# CCDGluing.net
KiCad netlist of a schematic drawn in EAGLE
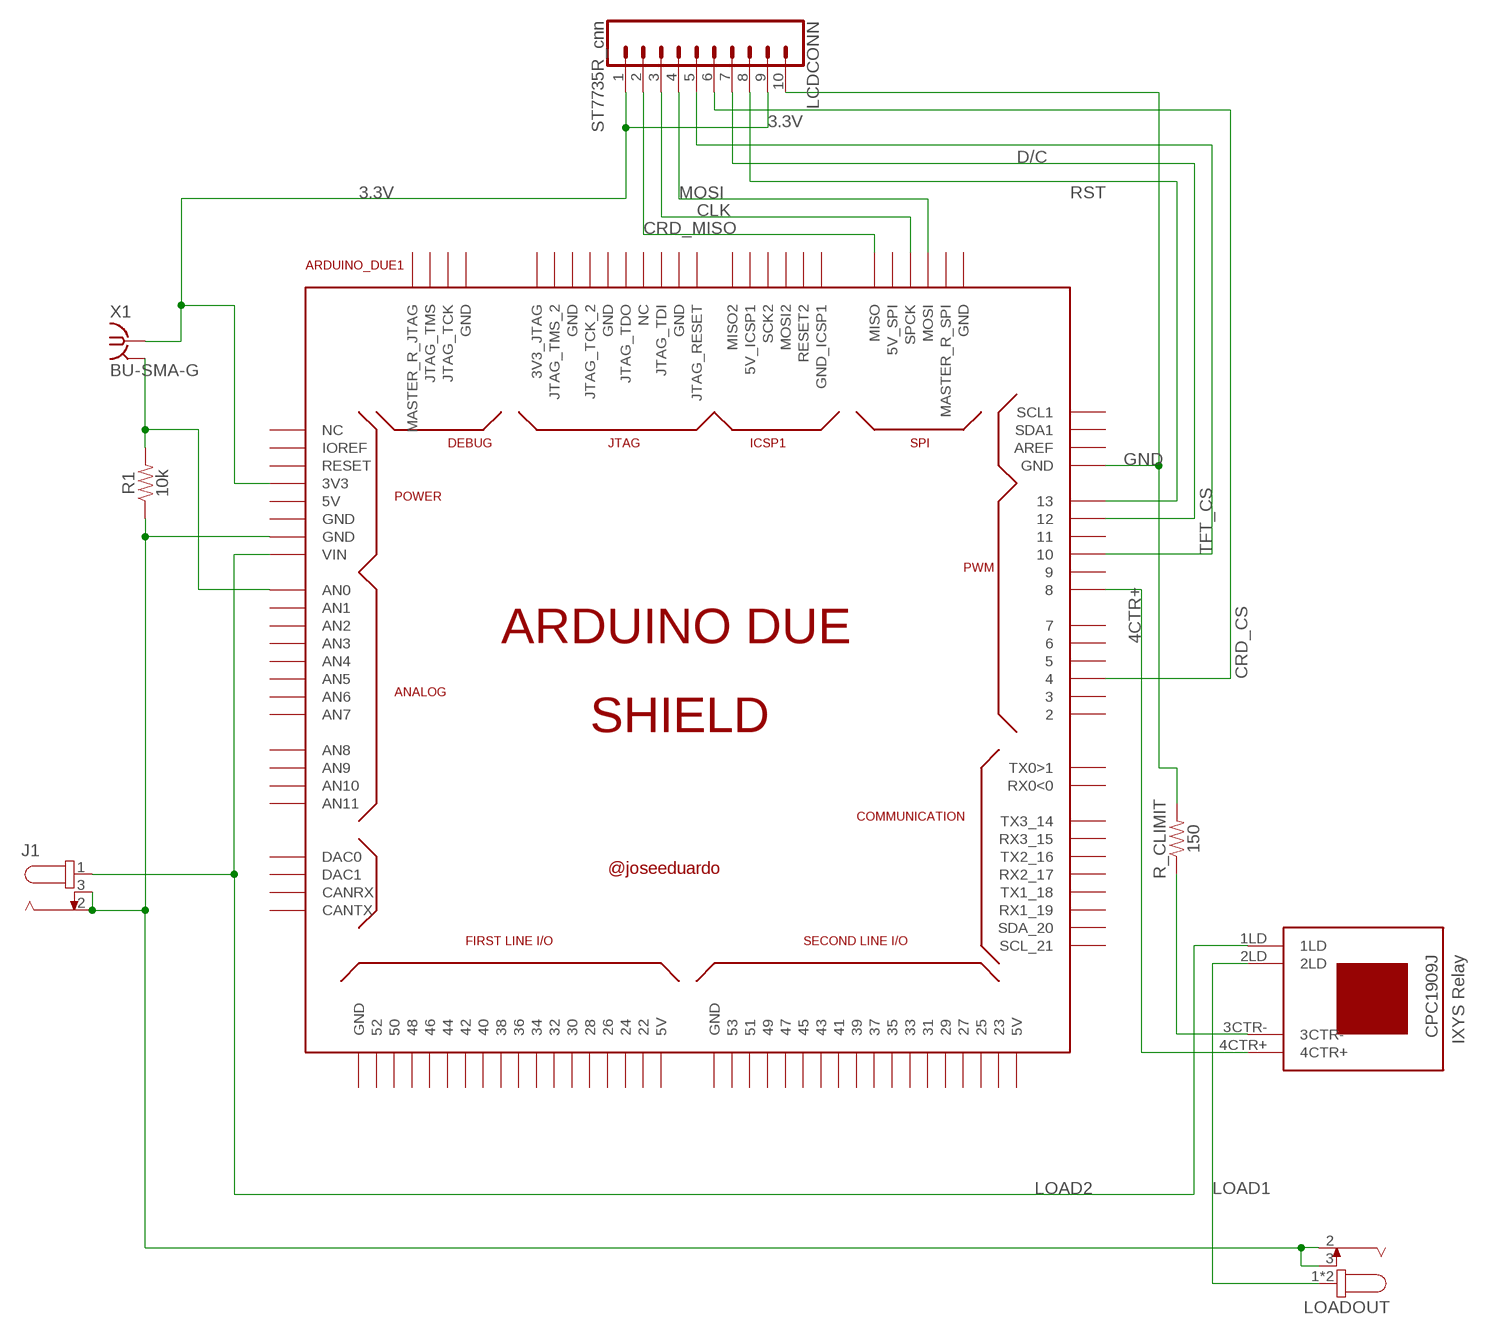
[diagram p0: schematic, sheet 1]

(export (version "E")
  (design (tool "Eeschema 10.0.6"))
  (components
    (comp (ref "ARDUINO_DUE1")
      (value "ARDUINO_DUE_SHIELD")
      (footprint "eagle-import:ARDUINO_DUE_SHIELD")
      (libsource (lib "eagle-import") (part "ARDUINO_DUE_SHIELD"))
    )
    (comp (ref "J1")
      (value "694106105102")
      (footprint "eagle-import:69410X105102")
      (libsource (lib "eagle-import") (part "694106105102"))
    )
    (comp (ref "K1")
      (value "CPC1909J")
      (footprint "eagle-import:CPC1909J")
      (libsource (lib "eagle-import") (part "CPC1909J"))
    )
    (comp (ref "LCDCONN")
      (value "ST7735R_cnn")
      (footprint "eagle-import:1X10")
      (libsource (lib "eagle-import") (part "CONN_10{dblquote}"))
    )
    (comp (ref "LOADOUT")
      (value "694103107102")
      (footprint "eagle-import:69410X107102")
      (libsource (lib "eagle-import") (part "694103107102"))
    )
    (comp (ref "R1")
      (value "10k")
      (footprint "eagle-import:0603")
      (libsource (lib "eagle-import") (part "10KOHM-0603-1/10W-1%"))
    )
    (comp (ref "R_CLIMIT")
      (value "150")
      (footprint "eagle-import:0603")
      (libsource (lib "eagle-import") (part "150OHM-0603-1/10W-1%"))
    )
    (comp (ref "X1")
      (value "BU-SMA-G")
      (footprint "eagle-import:BU-SMA-G")
      (libsource (lib "eagle-import") (part "BU-SMA-G"))
    )
  )
  (nets
    (net (code "1") (name "/3.3V") (class "Default")
      (node (ref "ARDUINO_DUE1") (pin "3V3") (pinfunction "3V3_3V3") (pintype "bidirectional"))
      (node (ref "LCDCONN") (pin "1") (pinfunction "1_1") (pintype "passive"))
      (node (ref "LCDCONN") (pin "9") (pinfunction "9_9") (pintype "passive"))
      (node (ref "X1") (pin "1") (pinfunction "1_1") (pintype "passive"))
    )
    (net (code "2") (name "/4CTR+") (class "Default")
      (node (ref "ARDUINO_DUE1") (pin "8") (pinfunction "8_8") (pintype "bidirectional"))
      (node (ref "K1") (pin "4CTR+") (pinfunction "4CTR+_4CTR+") (pintype "bidirectional"))
    )
    (net (code "3") (name "/CLK") (class "Default")
      (node (ref "ARDUINO_DUE1") (pin "SPCK") (pinfunction "SPCK_SPCK") (pintype "bidirectional"))
      (node (ref "LCDCONN") (pin "3") (pinfunction "3_3") (pintype "passive"))
    )
    (net (code "4") (name "/CRD_CS") (class "Default")
      (node (ref "ARDUINO_DUE1") (pin "4") (pinfunction "4_4") (pintype "bidirectional"))
      (node (ref "LCDCONN") (pin "6") (pinfunction "6_6") (pintype "passive"))
    )
    (net (code "5") (name "/CRD_MISO") (class "Default")
      (node (ref "ARDUINO_DUE1") (pin "MISO") (pinfunction "MISO_MISO") (pintype "bidirectional"))
      (node (ref "LCDCONN") (pin "2") (pinfunction "2_2") (pintype "passive"))
    )
    (net (code "6") (name "/D{slash}C") (class "Default")
      (node (ref "ARDUINO_DUE1") (pin "12") (pinfunction "12_12") (pintype "bidirectional"))
      (node (ref "LCDCONN") (pin "7") (pinfunction "7_7") (pintype "passive"))
    )
    (net (code "7") (name "/GND") (class "Default")
      (node (ref "ARDUINO_DUE1") (pin "GND_4") (pinfunction "GND_GND_4") (pintype "bidirectional"))
      (node (ref "LCDCONN") (pin "10") (pinfunction "10_10") (pintype "passive"))
      (node (ref "R_CLIMIT") (pin "2") (pinfunction "2_2") (pintype "passive"))
    )
    (net (code "8") (name "/LOAD1") (class "Default")
      (node (ref "K1") (pin "2LD") (pinfunction "2LD_2LD") (pintype "power_in"))
      (node (ref "LOADOUT") (pin "1") (pinfunction "1_1") (pintype "passive"))
      (node (ref "LOADOUT") (pin "A1") (pinfunction "1_A1") (pintype "passive"))
    )
    (net (code "9") (name "/LOAD2") (class "Default")
      (node (ref "ARDUINO_DUE1") (pin "VIN") (pinfunction "VIN_VIN") (pintype "bidirectional"))
      (node (ref "J1") (pin "1") (pinfunction "1_1") (pintype "passive"))
      (node (ref "K1") (pin "1LD") (pinfunction "1LD_1LD") (pintype "power_in"))
    )
    (net (code "10") (name "/MOSI") (class "Default")
      (node (ref "ARDUINO_DUE1") (pin "MOSI") (pinfunction "MOSI_MOSI") (pintype "bidirectional"))
      (node (ref "LCDCONN") (pin "4") (pinfunction "4_4") (pintype "passive"))
    )
    (net (code "11") (name "/RST") (class "Default")
      (node (ref "ARDUINO_DUE1") (pin "13") (pinfunction "13_13") (pintype "bidirectional"))
      (node (ref "LCDCONN") (pin "8") (pinfunction "8_8") (pintype "passive"))
    )
    (net (code "12") (name "/TFT_CS") (class "Default")
      (node (ref "ARDUINO_DUE1") (pin "10") (pinfunction "10_10") (pintype "bidirectional"))
      (node (ref "LCDCONN") (pin "5") (pinfunction "5_5") (pintype "passive"))
    )
    (net (code "13") (name "Net-(ARDUINO_DUE1-AN0)") (class "Default")
      (node (ref "ARDUINO_DUE1") (pin "A0") (pinfunction "AN0_A0") (pintype "bidirectional"))
      (node (ref "R1") (pin "2") (pinfunction "2_2") (pintype "passive"))
      (node (ref "X1") (pin "2") (pinfunction "2_2") (pintype "passive"))
      (node (ref "X1") (pin "3") (pinfunction "2_3") (pintype "passive"))
      (node (ref "X1") (pin "4") (pinfunction "2_4") (pintype "passive"))
      (node (ref "X1") (pin "5") (pinfunction "2_5") (pintype "passive"))
    )
    (net (code "14") (name "Net-(ARDUINO_DUE1-GND-PadGND_1)") (class "Default")
      (node (ref "ARDUINO_DUE1") (pin "GND_1") (pinfunction "GND_GND_1") (pintype "bidirectional"))
      (node (ref "J1") (pin "2") (pinfunction "2_2") (pintype "passive"))
      (node (ref "J1") (pin "3") (pinfunction "3_3") (pintype "passive"))
      (node (ref "LOADOUT") (pin "2") (pinfunction "2_2") (pintype "passive"))
      (node (ref "LOADOUT") (pin "3") (pinfunction "3_3") (pintype "passive"))
      (node (ref "R1") (pin "1") (pinfunction "1_1") (pintype "passive"))
    )
    (net (code "15") (name "Net-(K1-Pad3CTR-)") (class "Default")
      (node (ref "K1") (pin "3CTR-") (pinfunction "3CTR-_3CTR-") (pintype "bidirectional"))
      (node (ref "R_CLIMIT") (pin "1") (pinfunction "1_1") (pintype "passive"))
    )
    (net (code "16") (name "unconnected-(ARDUINO_DUE1-5V-Pad5V0)") (class "Default")
      (node (ref "ARDUINO_DUE1") (pin "5V0") (pinfunction "5V_5V0") (pintype "bidirectional"))
    )
    (net (code "17") (name "unconnected-(ARDUINO_DUE1-5V-Pad5V0_1)") (class "Default")
      (node (ref "ARDUINO_DUE1") (pin "5V0_1") (pinfunction "5V_5V0_1") (pintype "bidirectional"))
    )
    (net (code "18") (name "unconnected-(ARDUINO_DUE1-5V-Pad5V0_2)") (class "Default")
      (node (ref "ARDUINO_DUE1") (pin "5V0_2") (pinfunction "5V_5V0_2") (pintype "bidirectional"))
    )
    (net (code "19") (name "unconnected-(ARDUINO_DUE1-5V_SPI-Pad5V_2)") (class "Default")
      (node (ref "ARDUINO_DUE1") (pin "5V_2") (pinfunction "5V_SPI_5V_2") (pintype "bidirectional"))
    )
    (net (code "20") (name "unconnected-(ARDUINO_DUE1-AN1-PadA1)") (class "Default")
      (node (ref "ARDUINO_DUE1") (pin "A1") (pinfunction "AN1_A1") (pintype "bidirectional"))
    )
    (net (code "21") (name "unconnected-(ARDUINO_DUE1-AN2-PadA2)") (class "Default")
      (node (ref "ARDUINO_DUE1") (pin "A2") (pinfunction "AN2_A2") (pintype "bidirectional"))
    )
    (net (code "22") (name "unconnected-(ARDUINO_DUE1-AN3-PadA3)") (class "Default")
      (node (ref "ARDUINO_DUE1") (pin "A3") (pinfunction "AN3_A3") (pintype "bidirectional"))
    )
    (net (code "23") (name "unconnected-(ARDUINO_DUE1-AN4-PadA4)") (class "Default")
      (node (ref "ARDUINO_DUE1") (pin "A4") (pinfunction "AN4_A4") (pintype "bidirectional"))
    )
    (net (code "24") (name "unconnected-(ARDUINO_DUE1-AN5-PadA5)") (class "Default")
      (node (ref "ARDUINO_DUE1") (pin "A5") (pinfunction "AN5_A5") (pintype "bidirectional"))
    )
    (net (code "25") (name "unconnected-(ARDUINO_DUE1-AN6-PadA6)") (class "Default")
      (node (ref "ARDUINO_DUE1") (pin "A6") (pinfunction "AN6_A6") (pintype "bidirectional"))
    )
    (net (code "26") (name "unconnected-(ARDUINO_DUE1-AN7-PadA7)") (class "Default")
      (node (ref "ARDUINO_DUE1") (pin "A7") (pinfunction "AN7_A7") (pintype "bidirectional"))
    )
    (net (code "27") (name "unconnected-(ARDUINO_DUE1-AN8-PadA8)") (class "Default")
      (node (ref "ARDUINO_DUE1") (pin "A8") (pinfunction "AN8_A8") (pintype "bidirectional"))
    )
    (net (code "28") (name "unconnected-(ARDUINO_DUE1-AN9-PadA9)") (class "Default")
      (node (ref "ARDUINO_DUE1") (pin "A9") (pinfunction "AN9_A9") (pintype "bidirectional"))
    )
    (net (code "29") (name "unconnected-(ARDUINO_DUE1-AN10-PadA10)") (class "Default")
      (node (ref "ARDUINO_DUE1") (pin "A10") (pinfunction "AN10_A10") (pintype "bidirectional"))
    )
    (net (code "30") (name "unconnected-(ARDUINO_DUE1-AN11-PadA11)") (class "Default")
      (node (ref "ARDUINO_DUE1") (pin "A11") (pinfunction "AN11_A11") (pintype "bidirectional"))
    )
    (net (code "31") (name "unconnected-(ARDUINO_DUE1-GND-PadGND_2)") (class "Default")
      (node (ref "ARDUINO_DUE1") (pin "GND_2") (pinfunction "GND_GND_2") (pintype "bidirectional"))
    )
    (net (code "32") (name "unconnected-(ARDUINO_DUE1-GND-PadGND_3)") (class "Default")
      (node (ref "ARDUINO_DUE1") (pin "GND_3") (pinfunction "GND_GND_3") (pintype "bidirectional"))
    )
    (net (code "33") (name "unconnected-(ARDUINO_DUE1-GND-PadGND_5)") (class "Default")
      (node (ref "ARDUINO_DUE1") (pin "GND_5") (pinfunction "GND_GND_5") (pintype "bidirectional"))
    )
    (net (code "34") (name "unconnected-(ARDUINO_DUE1-GND-PadGND_7)") (class "Default")
      (node (ref "ARDUINO_DUE1") (pin "GND_7") (pinfunction "GND_GND_7") (pintype "bidirectional"))
    )
    (net (code "35") (name "unconnected-(ARDUINO_DUE1-GND-PadGND_8)") (class "Default")
      (node (ref "ARDUINO_DUE1") (pin "GND_8") (pinfunction "GND_GND_8") (pintype "bidirectional"))
    )
    (net (code "36") (name "unconnected-(ARDUINO_DUE1-GND-PadGND_9)") (class "Default")
      (node (ref "ARDUINO_DUE1") (pin "GND_9") (pinfunction "GND_GND_9") (pintype "bidirectional"))
    )
    (net (code "37") (name "unconnected-(ARDUINO_DUE1-GND-PadGND_10)") (class "Default")
      (node (ref "ARDUINO_DUE1") (pin "GND_10") (pinfunction "GND_GND_10") (pintype "bidirectional"))
    )
    (net (code "38") (name "unconnected-(ARDUINO_DUE1-MASTER_R_JTAG-PadMASTER_RESET_JTAG)") (class "Default")
      (node (ref "ARDUINO_DUE1") (pin "MASTER_RESET_JTAG") (pinfunction "MASTER_R_JTAG_MASTER_RESET_JTAG") (pintype "bidirectional"))
    )
    (net (code "39") (name "unconnected-(ARDUINO_DUE1-MASTER_R_SPI-PadMASTER_RESET_SPI)") (class "Default")
      (node (ref "ARDUINO_DUE1") (pin "MASTER_RESET_SPI") (pinfunction "MASTER_R_SPI_MASTER_RESET_SPI") (pintype "bidirectional"))
    )
    (net (code "40") (name "unconnected-(ARDUINO_DUE1-NC-PadNC_2)") (class "Default")
      (node (ref "ARDUINO_DUE1") (pin "NC_2") (pinfunction "NC_NC_2") (pintype "no_connect"))
    )
    (net (code "41") (name "unconnected-(ARDUINO_DUE1-NC-PadNC_5)") (class "Default")
      (node (ref "ARDUINO_DUE1") (pin "NC_5") (pinfunction "NC_NC_5") (pintype "bidirectional"))
    )
    (net (code "42") (name "unconnected-(ARDUINO_DUE1-Pad2)") (class "Default")
      (node (ref "ARDUINO_DUE1") (pin "2") (pinfunction "2_2") (pintype "bidirectional"))
    )
    (net (code "43") (name "unconnected-(ARDUINO_DUE1-Pad3)") (class "Default")
      (node (ref "ARDUINO_DUE1") (pin "3") (pinfunction "3_3") (pintype "bidirectional"))
    )
    (net (code "44") (name "unconnected-(ARDUINO_DUE1-Pad3V3_JTAG)") (class "Default")
      (node (ref "ARDUINO_DUE1") (pin "3V3_JTAG") (pinfunction "3V3_JTAG_3V3_JTAG") (pintype "bidirectional"))
    )
    (net (code "45") (name "unconnected-(ARDUINO_DUE1-Pad5)") (class "Default")
      (node (ref "ARDUINO_DUE1") (pin "5") (pinfunction "5_5") (pintype "bidirectional"))
    )
    (net (code "46") (name "unconnected-(ARDUINO_DUE1-Pad5V_ICSP1)") (class "Default")
      (node (ref "ARDUINO_DUE1") (pin "5V_ICSP1") (pinfunction "5V_ICSP1_5V_ICSP1") (pintype "bidirectional"))
    )
    (net (code "47") (name "unconnected-(ARDUINO_DUE1-Pad6)") (class "Default")
      (node (ref "ARDUINO_DUE1") (pin "6") (pinfunction "6_6") (pintype "bidirectional"))
    )
    (net (code "48") (name "unconnected-(ARDUINO_DUE1-Pad7)") (class "Default")
      (node (ref "ARDUINO_DUE1") (pin "7") (pinfunction "7_7") (pintype "bidirectional"))
    )
    (net (code "49") (name "unconnected-(ARDUINO_DUE1-Pad9)") (class "Default")
      (node (ref "ARDUINO_DUE1") (pin "9") (pinfunction "9_9") (pintype "bidirectional"))
    )
    (net (code "50") (name "unconnected-(ARDUINO_DUE1-Pad11)") (class "Default")
      (node (ref "ARDUINO_DUE1") (pin "11") (pinfunction "11_11") (pintype "bidirectional"))
    )
    (net (code "51") (name "unconnected-(ARDUINO_DUE1-Pad22)") (class "Default")
      (node (ref "ARDUINO_DUE1") (pin "22") (pinfunction "22_22") (pintype "bidirectional"))
    )
    (net (code "52") (name "unconnected-(ARDUINO_DUE1-Pad23)") (class "Default")
      (node (ref "ARDUINO_DUE1") (pin "23") (pinfunction "23_23") (pintype "bidirectional"))
    )
    (net (code "53") (name "unconnected-(ARDUINO_DUE1-Pad24)") (class "Default")
      (node (ref "ARDUINO_DUE1") (pin "24") (pinfunction "24_24") (pintype "bidirectional"))
    )
    (net (code "54") (name "unconnected-(ARDUINO_DUE1-Pad25)") (class "Default")
      (node (ref "ARDUINO_DUE1") (pin "25") (pinfunction "25_25") (pintype "bidirectional"))
    )
    (net (code "55") (name "unconnected-(ARDUINO_DUE1-Pad26)") (class "Default")
      (node (ref "ARDUINO_DUE1") (pin "26") (pinfunction "26_26") (pintype "bidirectional"))
    )
    (net (code "56") (name "unconnected-(ARDUINO_DUE1-Pad27)") (class "Default")
      (node (ref "ARDUINO_DUE1") (pin "27") (pinfunction "27_27") (pintype "bidirectional"))
    )
    (net (code "57") (name "unconnected-(ARDUINO_DUE1-Pad28)") (class "Default")
      (node (ref "ARDUINO_DUE1") (pin "28") (pinfunction "28_28") (pintype "bidirectional"))
    )
    (net (code "58") (name "unconnected-(ARDUINO_DUE1-Pad29)") (class "Default")
      (node (ref "ARDUINO_DUE1") (pin "29") (pinfunction "29_29") (pintype "bidirectional"))
    )
    (net (code "59") (name "unconnected-(ARDUINO_DUE1-Pad30)") (class "Default")
      (node (ref "ARDUINO_DUE1") (pin "30") (pinfunction "30_30") (pintype "bidirectional"))
    )
    (net (code "60") (name "unconnected-(ARDUINO_DUE1-Pad31)") (class "Default")
      (node (ref "ARDUINO_DUE1") (pin "31") (pinfunction "31_31") (pintype "bidirectional"))
    )
    (net (code "61") (name "unconnected-(ARDUINO_DUE1-Pad32)") (class "Default")
      (node (ref "ARDUINO_DUE1") (pin "32") (pinfunction "32_32") (pintype "bidirectional"))
    )
    (net (code "62") (name "unconnected-(ARDUINO_DUE1-Pad33)") (class "Default")
      (node (ref "ARDUINO_DUE1") (pin "33") (pinfunction "33_33") (pintype "bidirectional"))
    )
    (net (code "63") (name "unconnected-(ARDUINO_DUE1-Pad34)") (class "Default")
      (node (ref "ARDUINO_DUE1") (pin "34") (pinfunction "34_34") (pintype "bidirectional"))
    )
    (net (code "64") (name "unconnected-(ARDUINO_DUE1-Pad35)") (class "Default")
      (node (ref "ARDUINO_DUE1") (pin "35") (pinfunction "35_35") (pintype "bidirectional"))
    )
    (net (code "65") (name "unconnected-(ARDUINO_DUE1-Pad36)") (class "Default")
      (node (ref "ARDUINO_DUE1") (pin "36") (pinfunction "36_36") (pintype "bidirectional"))
    )
    (net (code "66") (name "unconnected-(ARDUINO_DUE1-Pad37)") (class "Default")
      (node (ref "ARDUINO_DUE1") (pin "37") (pinfunction "37_37") (pintype "bidirectional"))
    )
    (net (code "67") (name "unconnected-(ARDUINO_DUE1-Pad38)") (class "Default")
      (node (ref "ARDUINO_DUE1") (pin "38") (pinfunction "38_38") (pintype "bidirectional"))
    )
    (net (code "68") (name "unconnected-(ARDUINO_DUE1-Pad39)") (class "Default")
      (node (ref "ARDUINO_DUE1") (pin "39") (pinfunction "39_39") (pintype "bidirectional"))
    )
    (net (code "69") (name "unconnected-(ARDUINO_DUE1-Pad40)") (class "Default")
      (node (ref "ARDUINO_DUE1") (pin "40") (pinfunction "40_40") (pintype "bidirectional"))
    )
    (net (code "70") (name "unconnected-(ARDUINO_DUE1-Pad41)") (class "Default")
      (node (ref "ARDUINO_DUE1") (pin "41") (pinfunction "41_41") (pintype "bidirectional"))
    )
    (net (code "71") (name "unconnected-(ARDUINO_DUE1-Pad42)") (class "Default")
      (node (ref "ARDUINO_DUE1") (pin "42") (pinfunction "42_42") (pintype "bidirectional"))
    )
    (net (code "72") (name "unconnected-(ARDUINO_DUE1-Pad43)") (class "Default")
      (node (ref "ARDUINO_DUE1") (pin "43") (pinfunction "43_43") (pintype "bidirectional"))
    )
    (net (code "73") (name "unconnected-(ARDUINO_DUE1-Pad44)") (class "Default")
      (node (ref "ARDUINO_DUE1") (pin "44") (pinfunction "44_44") (pintype "bidirectional"))
    )
    (net (code "74") (name "unconnected-(ARDUINO_DUE1-Pad45)") (class "Default")
      (node (ref "ARDUINO_DUE1") (pin "45") (pinfunction "45_45") (pintype "bidirectional"))
    )
    (net (code "75") (name "unconnected-(ARDUINO_DUE1-Pad46)") (class "Default")
      (node (ref "ARDUINO_DUE1") (pin "46") (pinfunction "46_46") (pintype "bidirectional"))
    )
    (net (code "76") (name "unconnected-(ARDUINO_DUE1-Pad47)") (class "Default")
      (node (ref "ARDUINO_DUE1") (pin "47") (pinfunction "47_47") (pintype "bidirectional"))
    )
    (net (code "77") (name "unconnected-(ARDUINO_DUE1-Pad48)") (class "Default")
      (node (ref "ARDUINO_DUE1") (pin "48") (pinfunction "48_48") (pintype "bidirectional"))
    )
    (net (code "78") (name "unconnected-(ARDUINO_DUE1-Pad49)") (class "Default")
      (node (ref "ARDUINO_DUE1") (pin "49") (pinfunction "49_49") (pintype "bidirectional"))
    )
    (net (code "79") (name "unconnected-(ARDUINO_DUE1-Pad50)") (class "Default")
      (node (ref "ARDUINO_DUE1") (pin "50") (pinfunction "50_50") (pintype "bidirectional"))
    )
    (net (code "80") (name "unconnected-(ARDUINO_DUE1-Pad51)") (class "Default")
      (node (ref "ARDUINO_DUE1") (pin "51") (pinfunction "51_51") (pintype "bidirectional"))
    )
    (net (code "81") (name "unconnected-(ARDUINO_DUE1-Pad52)") (class "Default")
      (node (ref "ARDUINO_DUE1") (pin "52") (pinfunction "52_52") (pintype "bidirectional"))
    )
    (net (code "82") (name "unconnected-(ARDUINO_DUE1-Pad53)") (class "Default")
      (node (ref "ARDUINO_DUE1") (pin "53") (pinfunction "53_53") (pintype "bidirectional"))
    )
    (net (code "83") (name "unconnected-(ARDUINO_DUE1-PadAREF)") (class "Default")
      (node (ref "ARDUINO_DUE1") (pin "AREF") (pinfunction "AREF_AREF") (pintype "bidirectional"))
    )
    (net (code "84") (name "unconnected-(ARDUINO_DUE1-PadCANRX)") (class "Default")
      (node (ref "ARDUINO_DUE1") (pin "CANRX") (pinfunction "CANRX_CANRX") (pintype "bidirectional"))
    )
    (net (code "85") (name "unconnected-(ARDUINO_DUE1-PadCANTX)") (class "Default")
      (node (ref "ARDUINO_DUE1") (pin "CANTX") (pinfunction "CANTX_CANTX") (pintype "bidirectional"))
    )
    (net (code "86") (name "unconnected-(ARDUINO_DUE1-PadDAC0)") (class "Default")
      (node (ref "ARDUINO_DUE1") (pin "DAC0") (pinfunction "DAC0_DAC0") (pintype "bidirectional"))
    )
    (net (code "87") (name "unconnected-(ARDUINO_DUE1-PadDAC1)") (class "Default")
      (node (ref "ARDUINO_DUE1") (pin "DAC1") (pinfunction "DAC1_DAC1") (pintype "bidirectional"))
    )
    (net (code "88") (name "unconnected-(ARDUINO_DUE1-PadGND)") (class "Default")
      (node (ref "ARDUINO_DUE1") (pin "GND") (pinfunction "GND_GND") (pintype "bidirectional"))
    )
    (net (code "89") (name "unconnected-(ARDUINO_DUE1-PadGND_ICSP1)") (class "Default")
      (node (ref "ARDUINO_DUE1") (pin "GND_ICSP1") (pinfunction "GND_ICSP1_GND_ICSP1") (pintype "bidirectional"))
    )
    (net (code "90") (name "unconnected-(ARDUINO_DUE1-PadIOREF)") (class "Default")
      (node (ref "ARDUINO_DUE1") (pin "IOREF") (pinfunction "IOREF_IOREF") (pintype "bidirectional"))
    )
    (net (code "91") (name "unconnected-(ARDUINO_DUE1-PadJTAG_RESET)") (class "Default")
      (node (ref "ARDUINO_DUE1") (pin "JTAG_RESET") (pinfunction "JTAG_RESET_JTAG_RESET") (pintype "bidirectional"))
    )
    (net (code "92") (name "unconnected-(ARDUINO_DUE1-PadJTAG_TCK)") (class "Default")
      (node (ref "ARDUINO_DUE1") (pin "JTAG_TCK") (pinfunction "JTAG_TCK_JTAG_TCK") (pintype "bidirectional"))
    )
    (net (code "93") (name "unconnected-(ARDUINO_DUE1-PadJTAG_TCK_2)") (class "Default")
      (node (ref "ARDUINO_DUE1") (pin "JTAG_TCK_2") (pinfunction "JTAG_TCK_2_JTAG_TCK_2") (pintype "bidirectional"))
    )
    (net (code "94") (name "unconnected-(ARDUINO_DUE1-PadJTAG_TDI)") (class "Default")
      (node (ref "ARDUINO_DUE1") (pin "JTAG_TDI") (pinfunction "JTAG_TDI_JTAG_TDI") (pintype "bidirectional"))
    )
    (net (code "95") (name "unconnected-(ARDUINO_DUE1-PadJTAG_TDO)") (class "Default")
      (node (ref "ARDUINO_DUE1") (pin "JTAG_TDO") (pinfunction "JTAG_TDO_JTAG_TDO") (pintype "bidirectional"))
    )
    (net (code "96") (name "unconnected-(ARDUINO_DUE1-PadJTAG_TMS)") (class "Default")
      (node (ref "ARDUINO_DUE1") (pin "JTAG_TMS") (pinfunction "JTAG_TMS_JTAG_TMS") (pintype "bidirectional"))
    )
    (net (code "97") (name "unconnected-(ARDUINO_DUE1-PadJTAG_TMS_2)") (class "Default")
      (node (ref "ARDUINO_DUE1") (pin "JTAG_TMS_2") (pinfunction "JTAG_TMS_2_JTAG_TMS_2") (pintype "bidirectional"))
    )
    (net (code "98") (name "unconnected-(ARDUINO_DUE1-PadMISO2)") (class "Default")
      (node (ref "ARDUINO_DUE1") (pin "MISO2") (pinfunction "MISO2_MISO2") (pintype "bidirectional"))
    )
    (net (code "99") (name "unconnected-(ARDUINO_DUE1-PadMOSI2)") (class "Default")
      (node (ref "ARDUINO_DUE1") (pin "MOSI2") (pinfunction "MOSI2_MOSI2") (pintype "bidirectional"))
    )
    (net (code "100") (name "unconnected-(ARDUINO_DUE1-PadRESET)") (class "Default")
      (node (ref "ARDUINO_DUE1") (pin "RESET") (pinfunction "RESET_RESET") (pintype "bidirectional"))
    )
    (net (code "101") (name "unconnected-(ARDUINO_DUE1-PadRESET2)") (class "Default")
      (node (ref "ARDUINO_DUE1") (pin "RESET2") (pinfunction "RESET2_RESET2") (pintype "bidirectional"))
    )
    (net (code "102") (name "unconnected-(ARDUINO_DUE1-PadSCK2)") (class "Default")
      (node (ref "ARDUINO_DUE1") (pin "SCK2") (pinfunction "SCK2_SCK2") (pintype "bidirectional"))
    )
    (net (code "103") (name "unconnected-(ARDUINO_DUE1-PadSCL1)") (class "Default")
      (node (ref "ARDUINO_DUE1") (pin "SCL1") (pinfunction "SCL1_SCL1") (pintype "bidirectional"))
    )
    (net (code "104") (name "unconnected-(ARDUINO_DUE1-PadSDA1)") (class "Default")
      (node (ref "ARDUINO_DUE1") (pin "SDA1") (pinfunction "SDA1_SDA1") (pintype "bidirectional"))
    )
    (net (code "105") (name "unconnected-(ARDUINO_DUE1-RX0<0-Pad0)") (class "Default")
      (node (ref "ARDUINO_DUE1") (pin "0") (pinfunction "RX0<0_0") (pintype "bidirectional"))
    )
    (net (code "106") (name "unconnected-(ARDUINO_DUE1-RX1_19-Pad19)") (class "Default")
      (node (ref "ARDUINO_DUE1") (pin "19") (pinfunction "RX1_19_19") (pintype "bidirectional"))
    )
    (net (code "107") (name "unconnected-(ARDUINO_DUE1-RX2_17-Pad17)") (class "Default")
      (node (ref "ARDUINO_DUE1") (pin "17") (pinfunction "RX2_17_17") (pintype "bidirectional"))
    )
    (net (code "108") (name "unconnected-(ARDUINO_DUE1-RX3_15-Pad15)") (class "Default")
      (node (ref "ARDUINO_DUE1") (pin "15") (pinfunction "RX3_15_15") (pintype "bidirectional"))
    )
    (net (code "109") (name "unconnected-(ARDUINO_DUE1-SCL_21-Pad21)") (class "Default")
      (node (ref "ARDUINO_DUE1") (pin "21") (pinfunction "SCL_21_21") (pintype "bidirectional"))
    )
    (net (code "110") (name "unconnected-(ARDUINO_DUE1-SDA_20-Pad20)") (class "Default")
      (node (ref "ARDUINO_DUE1") (pin "20") (pinfunction "SDA_20_20") (pintype "bidirectional"))
    )
    (net (code "111") (name "unconnected-(ARDUINO_DUE1-TX0>1-Pad1)") (class "Default")
      (node (ref "ARDUINO_DUE1") (pin "1") (pinfunction "TX0>1_1") (pintype "bidirectional"))
    )
    (net (code "112") (name "unconnected-(ARDUINO_DUE1-TX1_18-Pad18)") (class "Default")
      (node (ref "ARDUINO_DUE1") (pin "18") (pinfunction "TX1_18_18") (pintype "bidirectional"))
    )
    (net (code "113") (name "unconnected-(ARDUINO_DUE1-TX2_16-Pad16)") (class "Default")
      (node (ref "ARDUINO_DUE1") (pin "16") (pinfunction "TX2_16_16") (pintype "bidirectional"))
    )
    (net (code "114") (name "unconnected-(ARDUINO_DUE1-TX3_14-Pad14)") (class "Default")
      (node (ref "ARDUINO_DUE1") (pin "14") (pinfunction "TX3_14_14") (pintype "bidirectional"))
    )
  )
)
